# ELKS.net
KiCad netlist of a schematic drawn in EasyEDA Pro
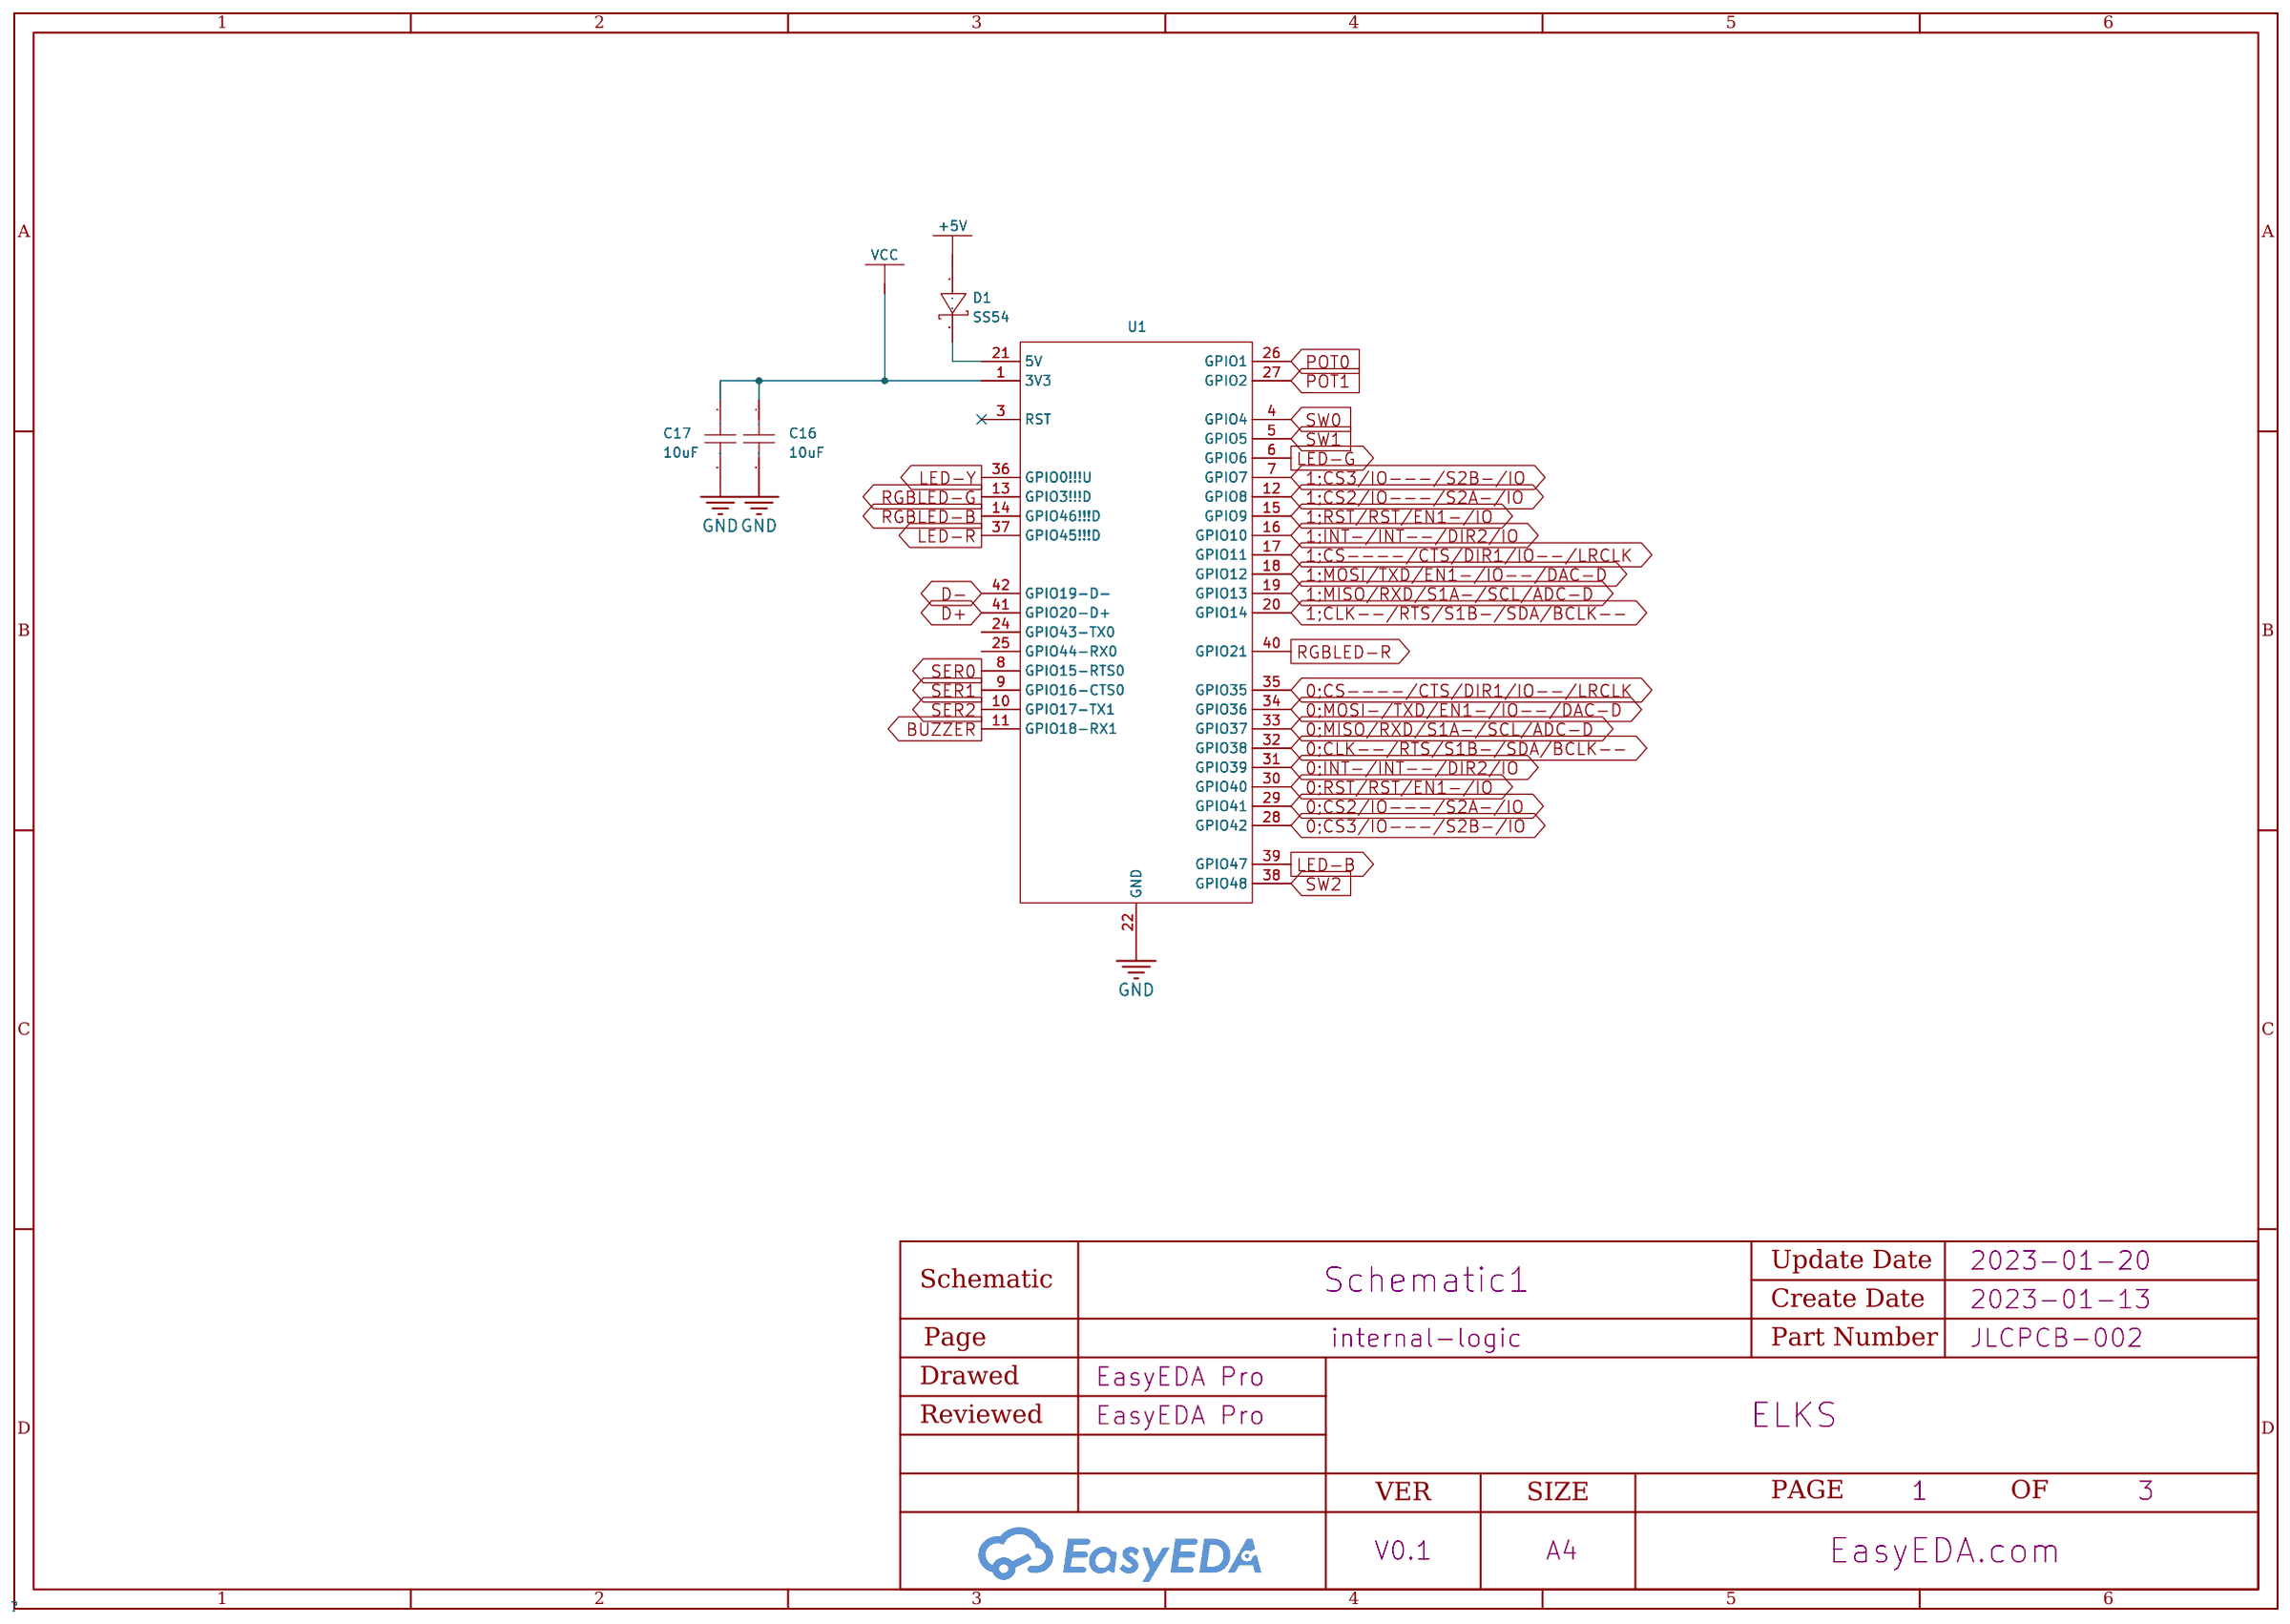
[diagram p0: internal-logic]
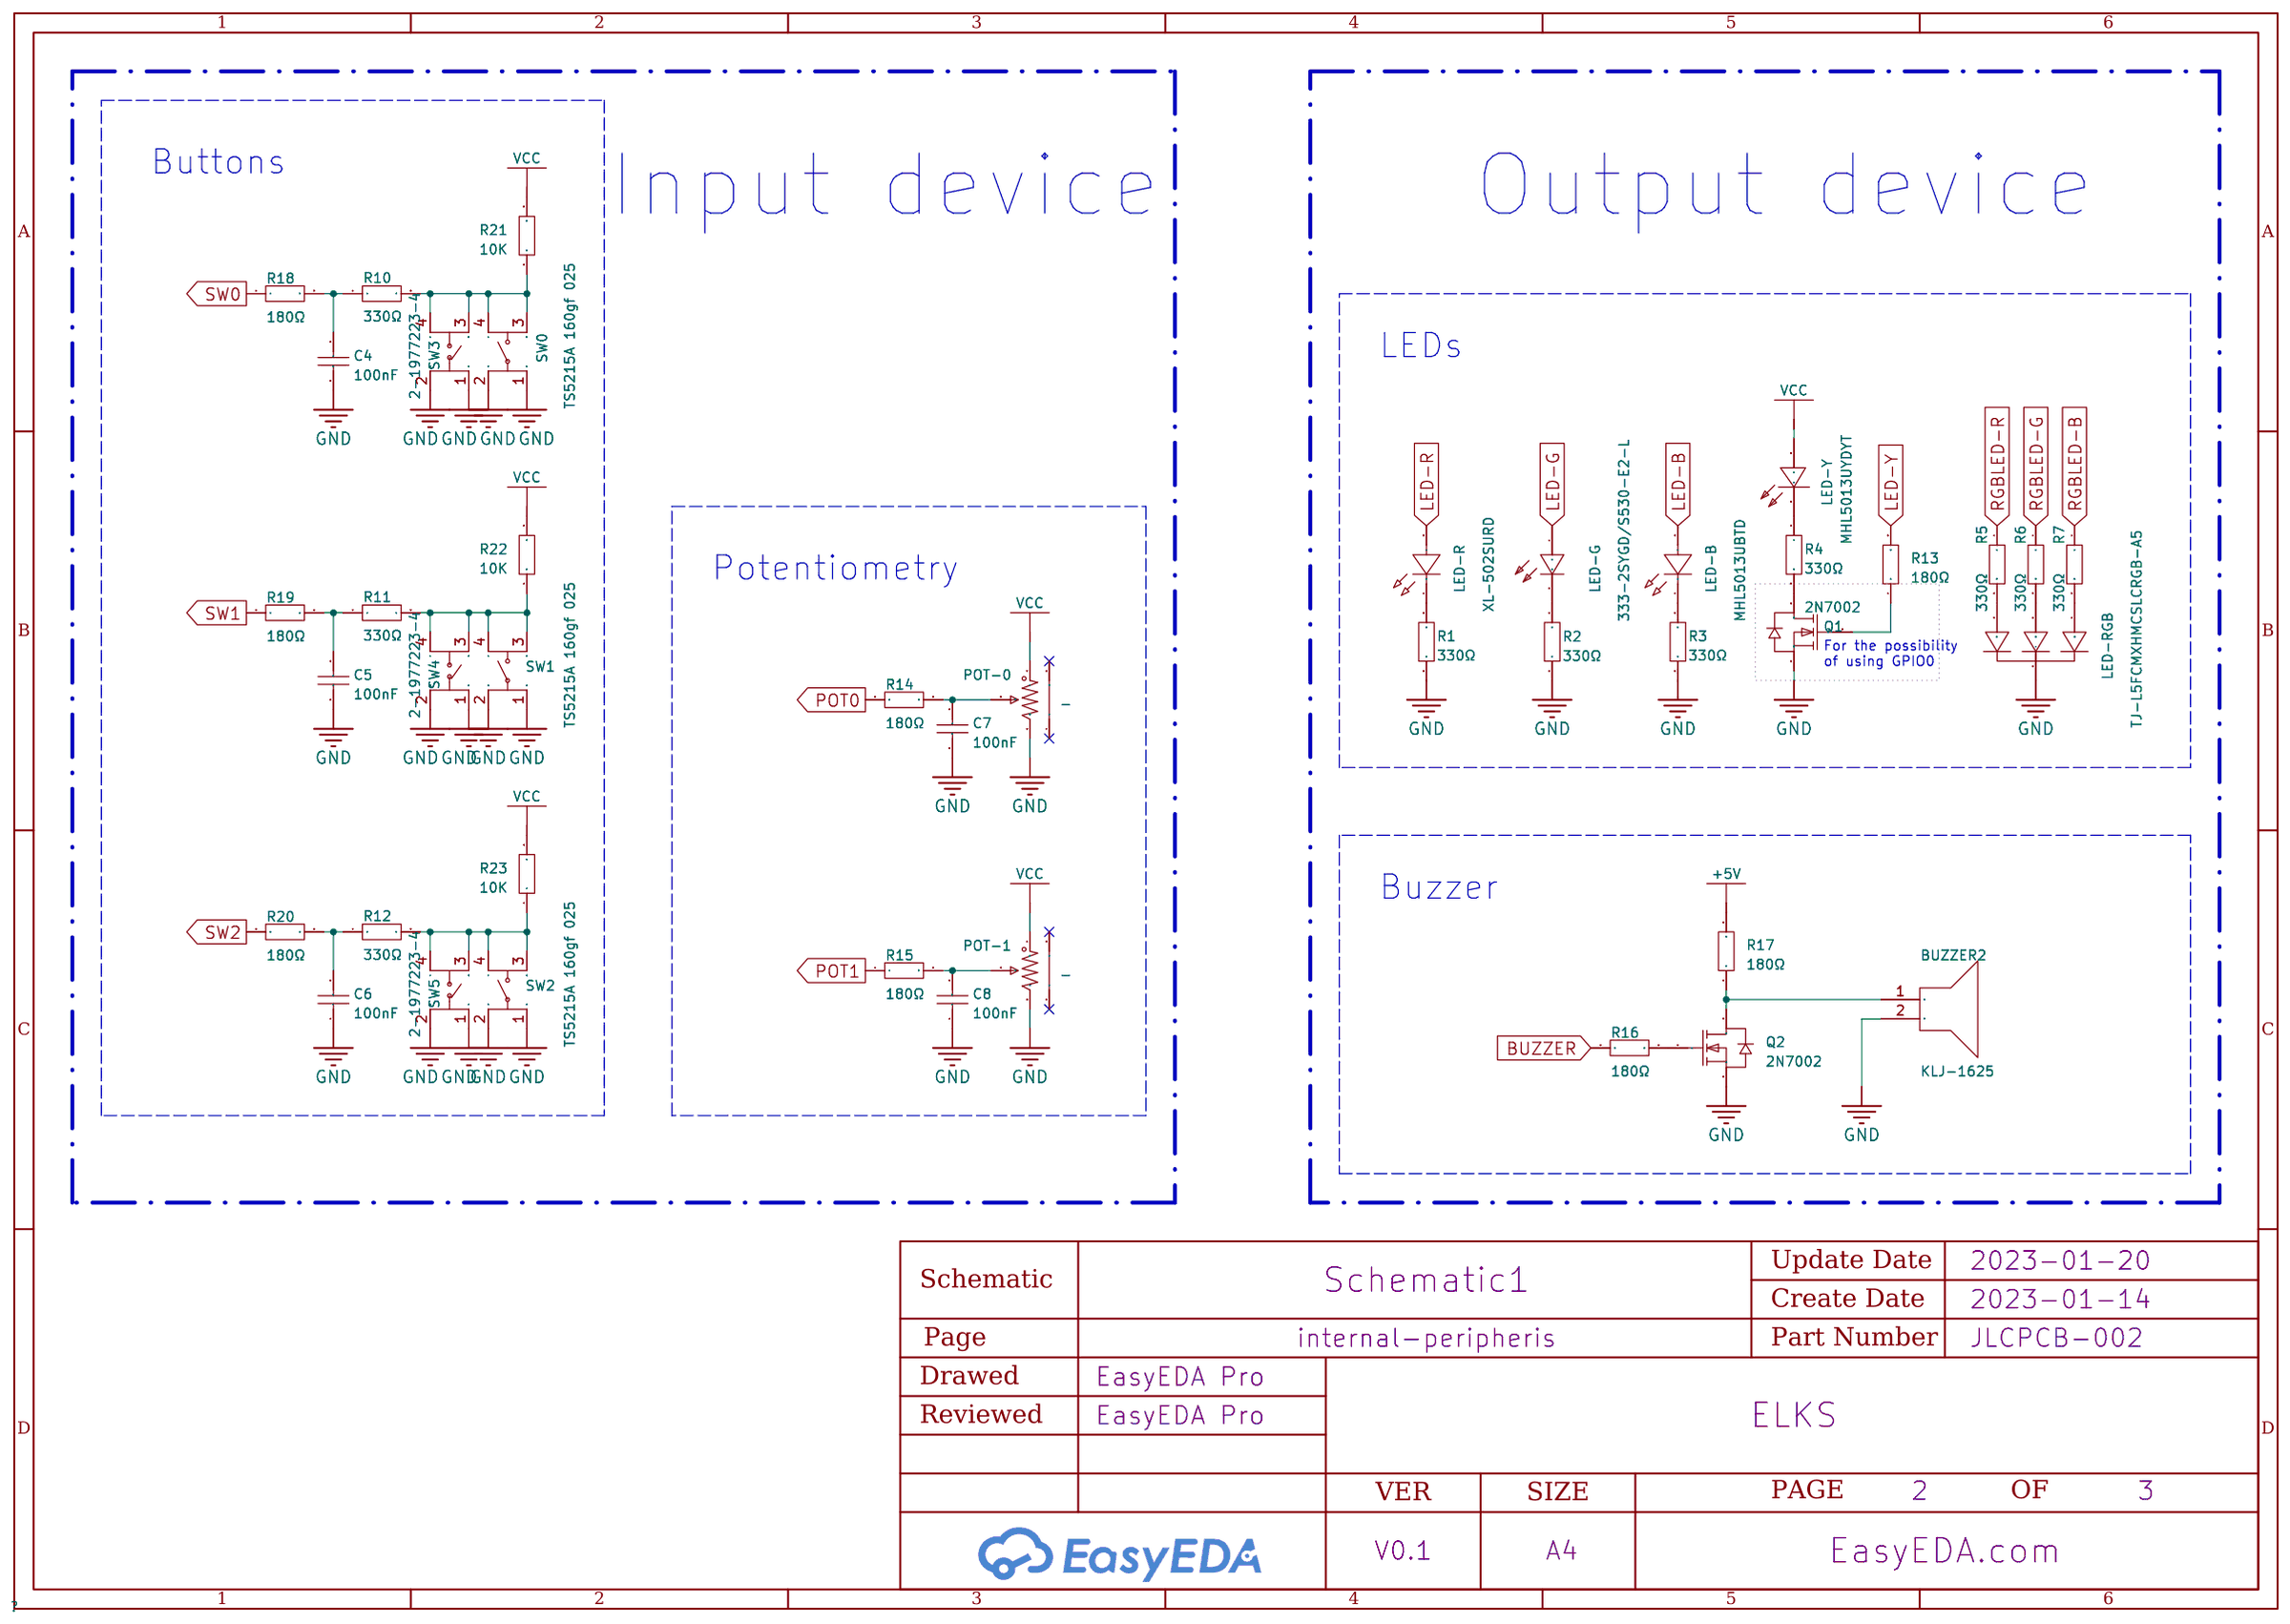
[diagram p1: internal-peripheris]
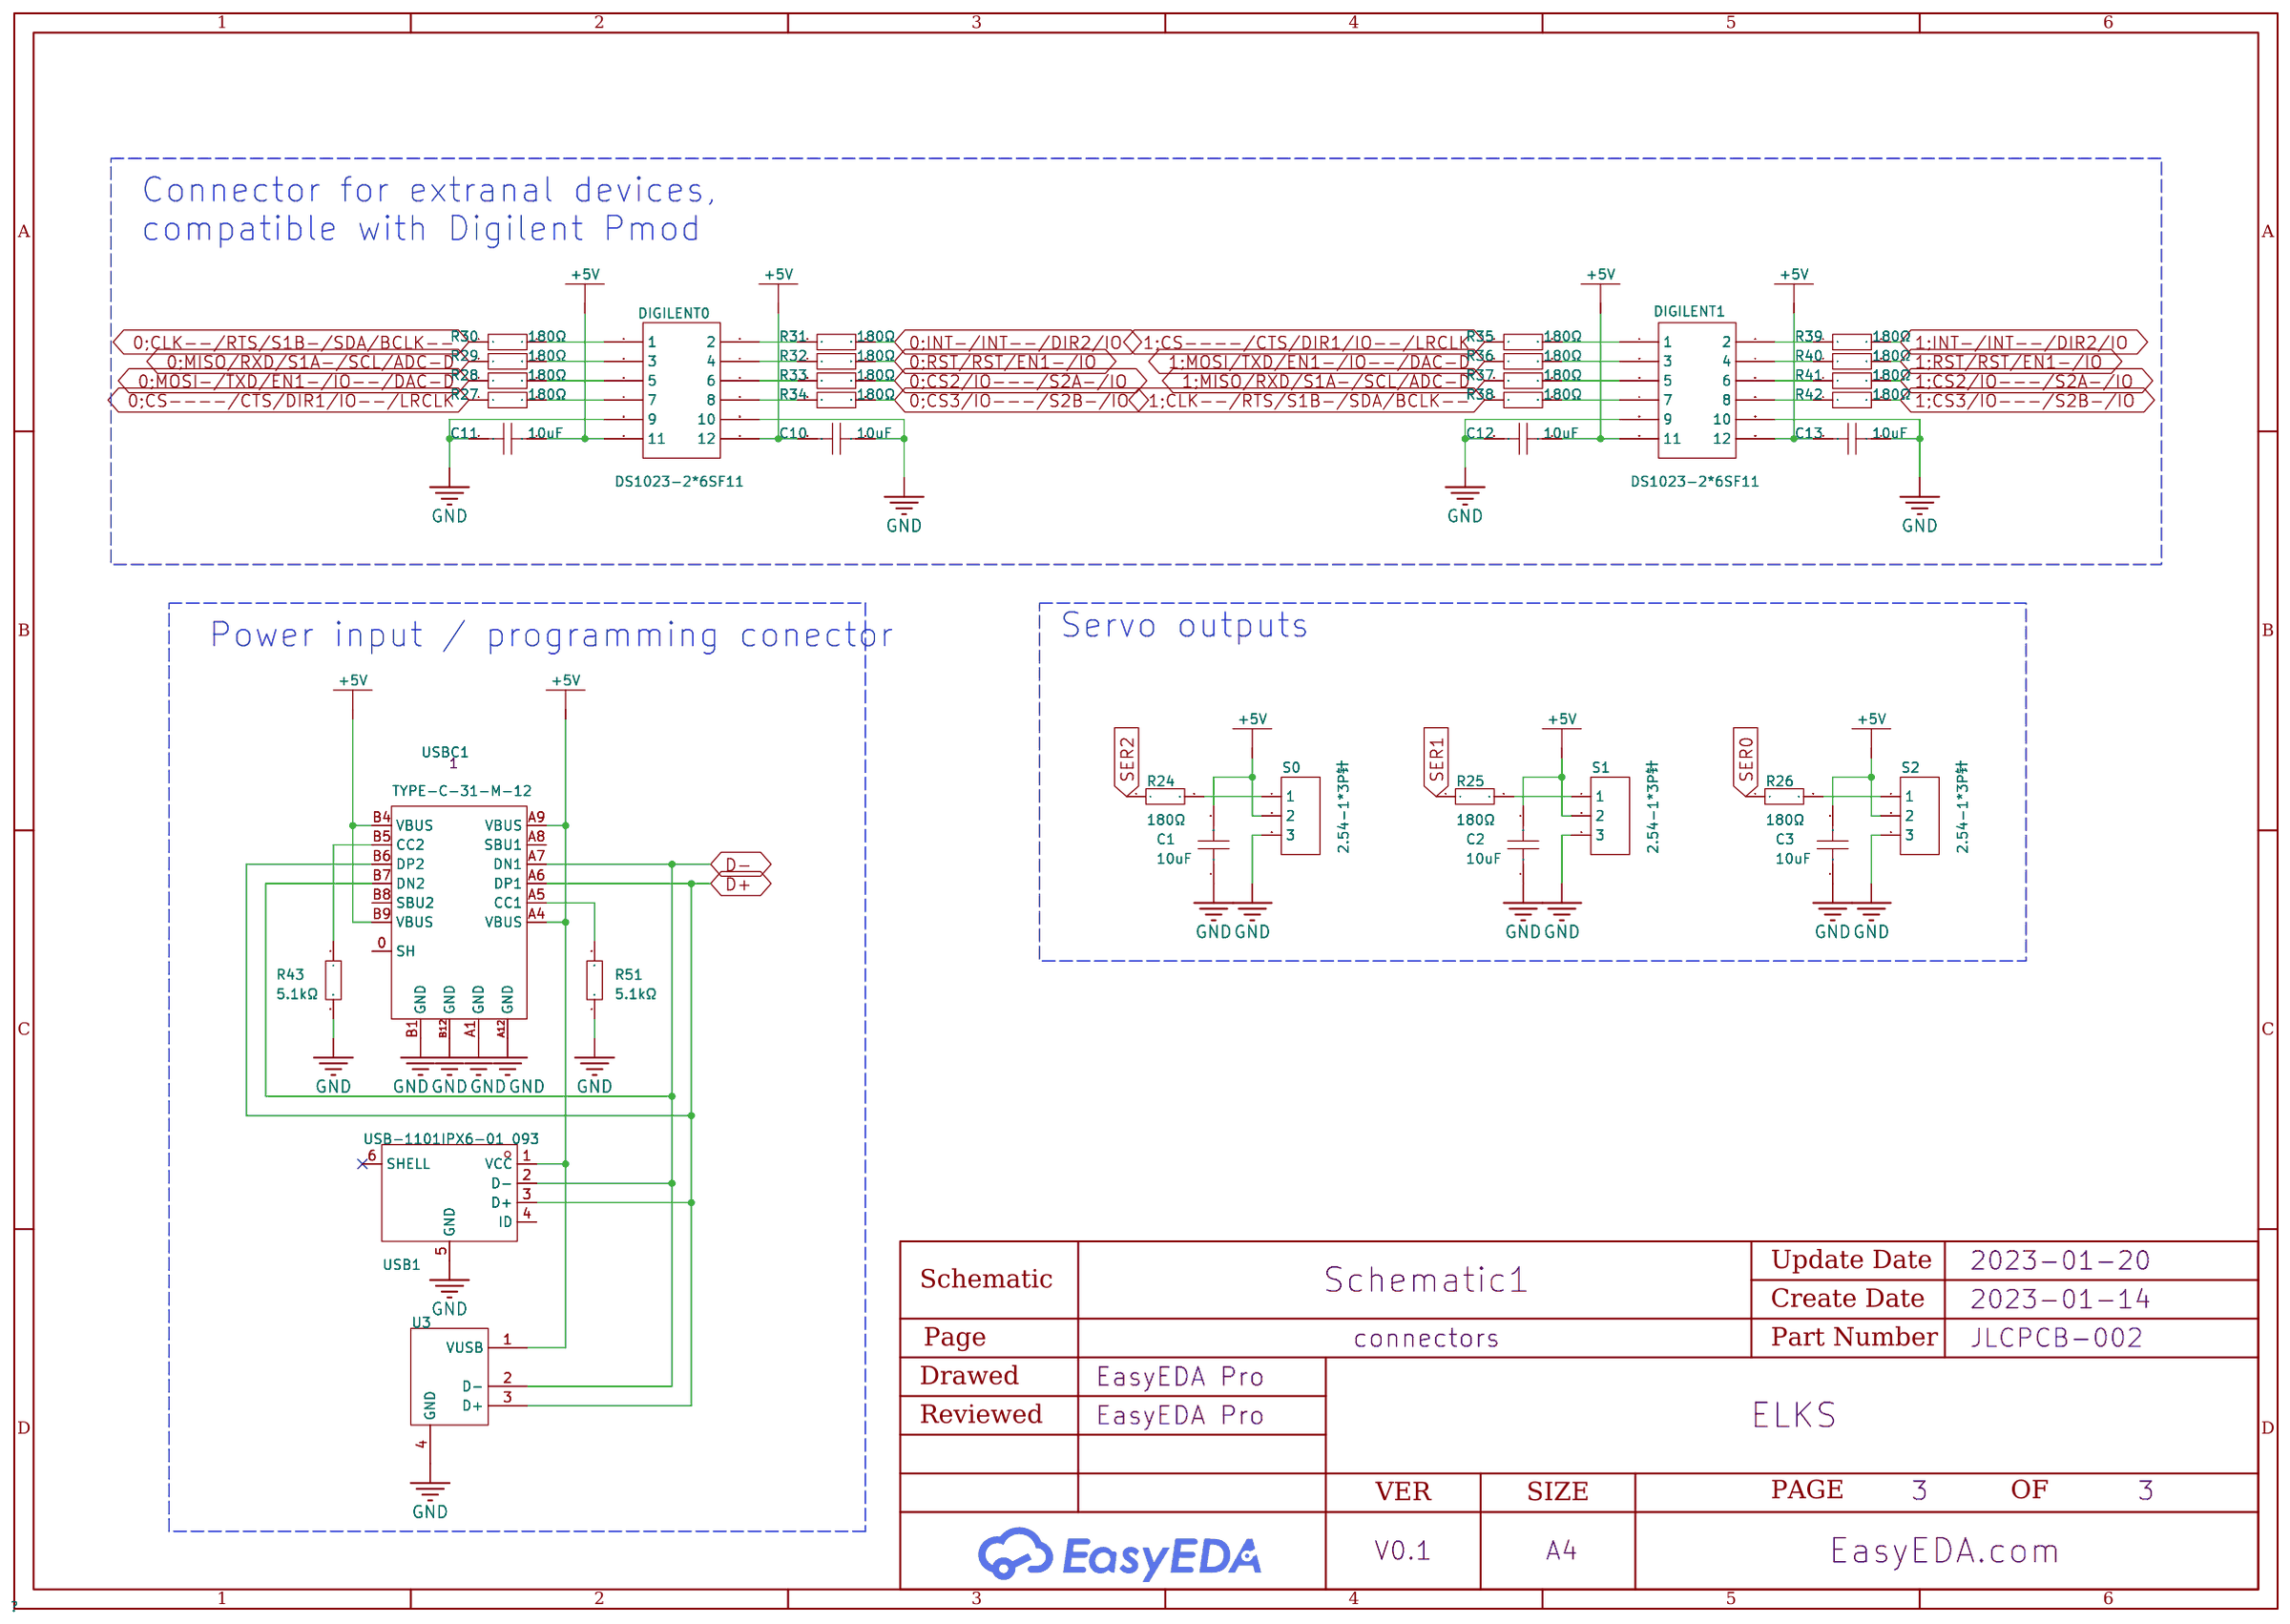
[diagram p2: connectors]

(export (version "E")
  (design (tool "Eeschema 10.0.6"))
  (components
    (comp (ref "C16")
      (value "10uF")
      (footprint "easyedapro:C0603")
      (fields
        (field (name "Manufacturer Part") "CL10A106MA8NRNC")
        (field (name "Manufacturer") "SAMSUNG(三星)")
        (field (name "Tolerance") "±20%")
      )
      (libsource (lib "easyedapro") (part "CL10A106MA8NRNC"))
    )
    (comp (ref "C17")
      (value "10uF")
      (footprint "easyedapro:C0603")
      (fields
        (field (name "Manufacturer Part") "CL10A106MA8NRNC")
        (field (name "Manufacturer") "SAMSUNG(三星)")
        (field (name "Tolerance") "±20%")
      )
      (libsource (lib "easyedapro") (part "CL10A106MA8NRNC"))
    )
    (comp (ref "D1")
      (value "SS54")
      (footprint "easyedapro:SMA_L4.4-W2.8-LS5.4-R-RD")
      (description "Reverse Voltage (Vr):40V Average Rectified Current (Io):5A Forward Voltage (Vf@If):550mV@5A")
      (fields (field (name "Manufacturer") "MDD"))
      (libsource (lib "easyedapro") (part "SS54_C22452"))
    )
    (comp (ref "U1") (value "~") (libsource (lib "easyedapro") (part "ESP32-S3-DevKitC-1")))
    (comp (ref "BUZZER2")
      (value "KLJ-1625")
      (footprint "easyedapro:BUZ-SMD_L16.0-W16.0")
      (fields (field (name "Manufacturer") "KELIKING(凯丽金)"))
      (libsource (lib "easyedapro") (part "KLJ-1625"))
    )
    (comp (ref "C4")
      (value "100nF")
      (footprint "easyedapro:C0402_NEW")
      (fields
        (field (name "Manufacturer Part") "CL05B104KO5NNNC")
        (field (name "Manufacturer") "SAMSUNG(三星)")
        (field (name "Tolerance") "±10%")
      )
      (libsource (lib "easyedapro") (part "CL05B104KO5NNNC"))
    )
    (comp (ref "C5")
      (value "100nF")
      (footprint "easyedapro:C0402_NEW")
      (fields
        (field (name "Manufacturer Part") "CL05B104KO5NNNC")
        (field (name "Manufacturer") "SAMSUNG(三星)")
        (field (name "Tolerance") "±10%")
      )
      (libsource (lib "easyedapro") (part "CL05B104KO5NNNC"))
    )
    (comp (ref "C6")
      (value "100nF")
      (footprint "easyedapro:C0402_NEW")
      (fields
        (field (name "Manufacturer Part") "CL05B104KO5NNNC")
        (field (name "Manufacturer") "SAMSUNG(三星)")
        (field (name "Tolerance") "±10%")
      )
      (libsource (lib "easyedapro") (part "CL05B104KO5NNNC"))
    )
    (comp (ref "C7")
      (value "100nF")
      (footprint "easyedapro:C0402_NEW")
      (fields
        (field (name "Manufacturer Part") "CL05B104KO5NNNC")
        (field (name "Manufacturer") "SAMSUNG(三星)")
        (field (name "Tolerance") "±10%")
      )
      (libsource (lib "easyedapro") (part "CL05B104KO5NNNC"))
    )
    (comp (ref "C8")
      (value "100nF")
      (footprint "easyedapro:C0402_NEW")
      (fields
        (field (name "Manufacturer Part") "CL05B104KO5NNNC")
        (field (name "Manufacturer") "SAMSUNG(三星)")
        (field (name "Tolerance") "±10%")
      )
      (libsource (lib "easyedapro") (part "CL05B104KO5NNNC"))
    )
    (comp (ref "LED-B")
      (value "MHL5013UBTD")
      (footprint "easyedapro:LED-TH_BD5.0-P2.54-L-RD_BLUE")
      (fields (field (name "Manufacturer") "MEIHUA(美华)"))
      (libsource (lib "easyedapro") (part "MHL5013UBTD"))
    )
    (comp (ref "LED-G")
      (value "333-2SYGD/S530-E2-L")
      (footprint "easyedapro:LED-TH_BD5.0-P2.54-FD")
      (fields (field (name "Manufacturer") "EVERLIGHT(亿光)"))
      (libsource (lib "easyedapro") (part "333-2SYGD/S530-E2-L"))
    )
    (comp (ref "LED-R")
      (value "XL-502SURD")
      (footprint "easyedapro:LED-TH_BD5.9-P2.54-RD_RED")
      (fields (field (name "Manufacturer") "XINGLIGHT(成兴光)"))
      (libsource (lib "easyedapro") (part "XL-502SURD"))
    )
    (comp (ref "LED-RGB")
      (value "TJ-L5FCMXHMCSLCRGB-A5")
      (footprint "easyedapro:LED-TH_4P-BD5.8-P1.30")
      (fields (field (name "Manufacturer") "TOGIALED(统佳)"))
      (libsource (lib "easyedapro") (part "TJ-L5FCMXHMCSLCRGB-A5"))
    )
    (comp (ref "LED-Y")
      (value "MHL5013UYDYT")
      (footprint "easyedapro:LED-TH_BD5.0-P2.54-L-RD_YELLOW")
      (fields (field (name "Manufacturer") "MEIHUA(美华)"))
      (libsource (lib "easyedapro") (part "MHL5013UYDYT"))
    )
    (comp (ref "POT-0")
      (value "-")
      (footprint "easyedapro:RES-ADJ-TH_RK09D1130C4G")
      (fields
        (field (name "Manufacturer Part") "RK09D1130C4G")
        (field (name "Manufacturer") "ALPSALPINE(阿尔卑斯阿尔派)")
      )
      (libsource (lib "easyedapro") (part "RK09D1130C4G"))
    )
    (comp (ref "POT-1")
      (value "-")
      (footprint "easyedapro:RES-ADJ-TH_RK09D1130C4G")
      (fields
        (field (name "Manufacturer Part") "RK09D1130C4G")
        (field (name "Manufacturer") "ALPSALPINE(阿尔卑斯阿尔派)")
      )
      (libsource (lib "easyedapro") (part "RK09D1130C4G"))
    )
    (comp (ref "Q1")
      (value "2N7002")
      (footprint "easyedapro:SOT-23-3_L2.9-W1.3-P1.90-LS2.4-BR")
      (fields (field (name "Manufacturer") "CJ(江苏长电/长晶)"))
      (libsource (lib "easyedapro") (part "2N7002"))
    )
    (comp (ref "Q2")
      (value "2N7002")
      (footprint "easyedapro:SOT-23-3_L2.9-W1.3-P1.90-LS2.4-BR")
      (fields (field (name "Manufacturer") "CJ(江苏长电/长晶)"))
      (libsource (lib "easyedapro") (part "2N7002"))
    )
    (comp (ref "R1")
      (value "330Ω")
      (footprint "easyedapro:R0603")
      (fields
        (field (name "Manufacturer Part") "0402WGF3300TCE")
        (field (name "Manufacturer") "UNI-ROYAL(厚声)")
      )
      (libsource (lib "easyedapro") (part "Res"))
    )
    (comp (ref "R2")
      (value "330Ω")
      (footprint "easyedapro:R0603")
      (fields
        (field (name "Manufacturer Part") "0402WGF3300TCE")
        (field (name "Manufacturer") "UNI-ROYAL(厚声)")
      )
      (libsource (lib "easyedapro") (part "Res"))
    )
    (comp (ref "R3")
      (value "330Ω")
      (footprint "easyedapro:R0603")
      (fields
        (field (name "Manufacturer Part") "0402WGF3300TCE")
        (field (name "Manufacturer") "UNI-ROYAL(厚声)")
      )
      (libsource (lib "easyedapro") (part "Res"))
    )
    (comp (ref "R4")
      (value "330Ω")
      (footprint "easyedapro:R0603")
      (fields
        (field (name "Manufacturer Part") "0402WGF3300TCE")
        (field (name "Manufacturer") "UNI-ROYAL(厚声)")
      )
      (libsource (lib "easyedapro") (part "Res"))
    )
    (comp (ref "R5")
      (value "330Ω")
      (footprint "easyedapro:R0603")
      (fields
        (field (name "Manufacturer Part") "0402WGF3300TCE")
        (field (name "Manufacturer") "UNI-ROYAL(厚声)")
      )
      (libsource (lib "easyedapro") (part "Res"))
    )
    (comp (ref "R6")
      (value "330Ω")
      (footprint "easyedapro:R0603")
      (fields
        (field (name "Manufacturer Part") "0402WGF3300TCE")
        (field (name "Manufacturer") "UNI-ROYAL(厚声)")
      )
      (libsource (lib "easyedapro") (part "Res"))
    )
    (comp (ref "R7")
      (value "330Ω")
      (footprint "easyedapro:R0603")
      (fields
        (field (name "Manufacturer Part") "0402WGF3300TCE")
        (field (name "Manufacturer") "UNI-ROYAL(厚声)")
      )
      (libsource (lib "easyedapro") (part "Res"))
    )
    (comp (ref "R10")
      (value "330Ω")
      (footprint "easyedapro:R0603")
      (fields
        (field (name "Manufacturer Part") "0402WGF3300TCE")
        (field (name "Manufacturer") "UNI-ROYAL(厚声)")
      )
      (libsource (lib "easyedapro") (part "Res"))
    )
    (comp (ref "R11")
      (value "330Ω")
      (footprint "easyedapro:R0603")
      (fields
        (field (name "Manufacturer Part") "0402WGF3300TCE")
        (field (name "Manufacturer") "UNI-ROYAL(厚声)")
      )
      (libsource (lib "easyedapro") (part "Res"))
    )
    (comp (ref "R12")
      (value "330Ω")
      (footprint "easyedapro:R0603")
      (fields
        (field (name "Manufacturer Part") "0402WGF3300TCE")
        (field (name "Manufacturer") "UNI-ROYAL(厚声)")
      )
      (libsource (lib "easyedapro") (part "Res"))
    )
    (comp (ref "R13")
      (value "180Ω")
      (footprint "easyedapro:R0603")
      (fields
        (field (name "Manufacturer Part") "0603WAF1800T5E")
        (field (name "Manufacturer") "UNI-ROYAL(厚声)")
      )
      (libsource (lib "easyedapro") (part "0603WAF1800T5E"))
    )
    (comp (ref "R14")
      (value "180Ω")
      (footprint "easyedapro:R0603")
      (fields
        (field (name "Manufacturer Part") "0603WAF1800T5E")
        (field (name "Manufacturer") "UNI-ROYAL(厚声)")
      )
      (libsource (lib "easyedapro") (part "0603WAF1800T5E"))
    )
    (comp (ref "R15")
      (value "180Ω")
      (footprint "easyedapro:R0603")
      (fields
        (field (name "Manufacturer Part") "0603WAF1800T5E")
        (field (name "Manufacturer") "UNI-ROYAL(厚声)")
      )
      (libsource (lib "easyedapro") (part "0603WAF1800T5E"))
    )
    (comp (ref "R16")
      (value "180Ω")
      (footprint "easyedapro:R0603")
      (fields
        (field (name "Manufacturer Part") "0603WAF1800T5E")
        (field (name "Manufacturer") "UNI-ROYAL(厚声)")
      )
      (libsource (lib "easyedapro") (part "0603WAF1800T5E"))
    )
    (comp (ref "R17")
      (value "180Ω")
      (footprint "easyedapro:R0603")
      (fields
        (field (name "Manufacturer Part") "0603WAF1800T5E")
        (field (name "Manufacturer") "UNI-ROYAL(厚声)")
      )
      (libsource (lib "easyedapro") (part "0603WAF1800T5E"))
    )
    (comp (ref "R18")
      (value "180Ω")
      (footprint "easyedapro:R0603")
      (fields
        (field (name "Manufacturer Part") "0603WAF1800T5E")
        (field (name "Manufacturer") "UNI-ROYAL(厚声)")
      )
      (libsource (lib "easyedapro") (part "0603WAF1800T5E"))
    )
    (comp (ref "R19")
      (value "180Ω")
      (footprint "easyedapro:R0603")
      (fields
        (field (name "Manufacturer Part") "0603WAF1800T5E")
        (field (name "Manufacturer") "UNI-ROYAL(厚声)")
      )
      (libsource (lib "easyedapro") (part "0603WAF1800T5E"))
    )
    (comp (ref "R20")
      (value "180Ω")
      (footprint "easyedapro:R0603")
      (fields
        (field (name "Manufacturer Part") "0603WAF1800T5E")
        (field (name "Manufacturer") "UNI-ROYAL(厚声)")
      )
      (libsource (lib "easyedapro") (part "0603WAF1800T5E"))
    )
    (comp (ref "R21")
      (value "10K")
      (footprint "easyedapro:R0603")
      (libsource (lib "easyedapro") (part "Res"))
    )
    (comp (ref "R22")
      (value "10K")
      (footprint "easyedapro:R0603")
      (libsource (lib "easyedapro") (part "Res"))
    )
    (comp (ref "R23")
      (value "10K")
      (footprint "easyedapro:R0603")
      (libsource (lib "easyedapro") (part "Res"))
    )
    (comp (ref "SW0")
      (value "TS5215A 160gf 025")
      (footprint "easyedapro:SW-SMD_4P-L5.2-W5.2-P3.70-LS6.4")
      (description "Switch Length:5.2mm Switch Width:5.2mm Switch Height:1.5mm")
      (fields (field (name "Manufacturer") "SHOU HAN(首韩)"))
      (libsource (lib "easyedapro") (part "TS5215A 160GF 025"))
    )
    (comp (ref "SW1")
      (value "TS5215A 160gf 025")
      (footprint "easyedapro:SW-SMD_4P-L5.2-W5.2-P3.70-LS6.4")
      (description "Switch Length:5.2mm Switch Width:5.2mm Switch Height:1.5mm")
      (fields (field (name "Manufacturer") "SHOU HAN(首韩)"))
      (libsource (lib "easyedapro") (part "TS5215A 160GF 025"))
    )
    (comp (ref "SW2")
      (value "TS5215A 160gf 025")
      (footprint "easyedapro:SW-SMD_4P-L5.2-W5.2-P3.70-LS6.4")
      (description "Switch Length:5.2mm Switch Width:5.2mm Switch Height:1.5mm")
      (fields (field (name "Manufacturer") "SHOU HAN(首韩)"))
      (libsource (lib "easyedapro") (part "TS5215A 160GF 025"))
    )
    (comp (ref "SW3")
      (value "2-1977223-4")
      (footprint "easyedapro:SW-SMD_4P-L6.0-W6.0-P4.50-LS10.0-BL")
      (fields (field (name "Manufacturer") "TE Connectivity(美国泰科)"))
      (libsource (lib "easyedapro") (part "2-1977223-4"))
    )
    (comp (ref "SW4")
      (value "2-1977223-4")
      (footprint "easyedapro:SW-SMD_4P-L6.0-W6.0-P4.50-LS10.0-BL")
      (fields (field (name "Manufacturer") "TE Connectivity(美国泰科)"))
      (libsource (lib "easyedapro") (part "2-1977223-4"))
    )
    (comp (ref "SW5")
      (value "2-1977223-4")
      (footprint "easyedapro:SW-SMD_4P-L6.0-W6.0-P4.50-LS10.0-BL")
      (fields (field (name "Manufacturer") "TE Connectivity(美国泰科)"))
      (libsource (lib "easyedapro") (part "2-1977223-4"))
    )
    (comp (ref "C1")
      (value "10uF")
      (footprint "easyedapro:C0603")
      (fields
        (field (name "Manufacturer Part") "CL10A106MA8NRNC")
        (field (name "Manufacturer") "SAMSUNG(三星)")
        (field (name "Tolerance") "±20%")
      )
      (libsource (lib "easyedapro") (part "CL10A106MA8NRNC"))
    )
    (comp (ref "C2")
      (value "10uF")
      (footprint "easyedapro:C0603")
      (fields
        (field (name "Manufacturer Part") "CL10A106MA8NRNC")
        (field (name "Manufacturer") "SAMSUNG(三星)")
        (field (name "Tolerance") "±20%")
      )
      (libsource (lib "easyedapro") (part "CL10A106MA8NRNC"))
    )
    (comp (ref "C3")
      (value "10uF")
      (footprint "easyedapro:C0603")
      (fields
        (field (name "Manufacturer Part") "CL10A106MA8NRNC")
        (field (name "Manufacturer") "SAMSUNG(三星)")
        (field (name "Tolerance") "±20%")
      )
      (libsource (lib "easyedapro") (part "CL10A106MA8NRNC"))
    )
    (comp (ref "C10")
      (value "10uF")
      (footprint "easyedapro:C0603")
      (fields
        (field (name "Manufacturer Part") "CL10A106MA8NRNC")
        (field (name "Manufacturer") "SAMSUNG(三星)")
        (field (name "Tolerance") "±20%")
      )
      (libsource (lib "easyedapro") (part "CL10A106MA8NRNC"))
    )
    (comp (ref "C11")
      (value "10uF")
      (footprint "easyedapro:C0603")
      (fields
        (field (name "Manufacturer Part") "CL10A106MA8NRNC")
        (field (name "Manufacturer") "SAMSUNG(三星)")
        (field (name "Tolerance") "±20%")
      )
      (libsource (lib "easyedapro") (part "CL10A106MA8NRNC"))
    )
    (comp (ref "C12")
      (value "10uF")
      (footprint "easyedapro:C0603")
      (fields
        (field (name "Manufacturer Part") "CL10A106MA8NRNC")
        (field (name "Manufacturer") "SAMSUNG(三星)")
        (field (name "Tolerance") "±20%")
      )
      (libsource (lib "easyedapro") (part "CL10A106MA8NRNC"))
    )
    (comp (ref "C13")
      (value "10uF")
      (footprint "easyedapro:C0603")
      (fields
        (field (name "Manufacturer Part") "CL10A106MA8NRNC")
        (field (name "Manufacturer") "SAMSUNG(三星)")
        (field (name "Tolerance") "±20%")
      )
      (libsource (lib "easyedapro") (part "CL10A106MA8NRNC"))
    )
    (comp (ref "DIGILENT0")
      (value "DS1023-2*6SF11")
      (footprint "easyedapro:HDR-TH_12P-P2.54-V-F-R2-C6-S2.54")
      (fields (field (name "Manufacturer") "CONNFLY"))
      (libsource (lib "easyedapro") (part "DS1023-2*6SF11"))
    )
    (comp (ref "DIGILENT1")
      (value "DS1023-2*6SF11")
      (footprint "easyedapro:HDR-TH_12P-P2.54-V-F-R2-C6-S2.54")
      (fields (field (name "Manufacturer") "CONNFLY"))
      (libsource (lib "easyedapro") (part "DS1023-2*6SF11"))
    )
    (comp (ref "R24")
      (value "180Ω")
      (footprint "easyedapro:R0603")
      (fields
        (field (name "Manufacturer Part") "0603WAF1800T5E")
        (field (name "Manufacturer") "UNI-ROYAL(厚声)")
      )
      (libsource (lib "easyedapro") (part "0603WAF1800T5E"))
    )
    (comp (ref "R25")
      (value "180Ω")
      (footprint "easyedapro:R0603")
      (fields
        (field (name "Manufacturer Part") "0603WAF1800T5E")
        (field (name "Manufacturer") "UNI-ROYAL(厚声)")
      )
      (libsource (lib "easyedapro") (part "0603WAF1800T5E"))
    )
    (comp (ref "R26")
      (value "180Ω")
      (footprint "easyedapro:R0603")
      (fields
        (field (name "Manufacturer Part") "0603WAF1800T5E")
        (field (name "Manufacturer") "UNI-ROYAL(厚声)")
      )
      (libsource (lib "easyedapro") (part "0603WAF1800T5E"))
    )
    (comp (ref "R27")
      (value "180Ω")
      (footprint "easyedapro:R0603")
      (fields
        (field (name "Manufacturer Part") "0603WAF1800T5E")
        (field (name "Manufacturer") "UNI-ROYAL(厚声)")
      )
      (libsource (lib "easyedapro") (part "0603WAF1800T5E"))
    )
    (comp (ref "R28")
      (value "180Ω")
      (footprint "easyedapro:R0603")
      (fields
        (field (name "Manufacturer Part") "0603WAF1800T5E")
        (field (name "Manufacturer") "UNI-ROYAL(厚声)")
      )
      (libsource (lib "easyedapro") (part "0603WAF1800T5E"))
    )
    (comp (ref "R29")
      (value "180Ω")
      (footprint "easyedapro:R0603")
      (fields
        (field (name "Manufacturer Part") "0603WAF1800T5E")
        (field (name "Manufacturer") "UNI-ROYAL(厚声)")
      )
      (libsource (lib "easyedapro") (part "0603WAF1800T5E"))
    )
    (comp (ref "R30")
      (value "180Ω")
      (footprint "easyedapro:R0603")
      (fields
        (field (name "Manufacturer Part") "0603WAF1800T5E")
        (field (name "Manufacturer") "UNI-ROYAL(厚声)")
      )
      (libsource (lib "easyedapro") (part "0603WAF1800T5E"))
    )
    (comp (ref "R31")
      (value "180Ω")
      (footprint "easyedapro:R0603")
      (fields
        (field (name "Manufacturer Part") "0603WAF1800T5E")
        (field (name "Manufacturer") "UNI-ROYAL(厚声)")
      )
      (libsource (lib "easyedapro") (part "0603WAF1800T5E"))
    )
    (comp (ref "R32")
      (value "180Ω")
      (footprint "easyedapro:R0603")
      (fields
        (field (name "Manufacturer Part") "0603WAF1800T5E")
        (field (name "Manufacturer") "UNI-ROYAL(厚声)")
      )
      (libsource (lib "easyedapro") (part "0603WAF1800T5E"))
    )
    (comp (ref "R33")
      (value "180Ω")
      (footprint "easyedapro:R0603")
      (fields
        (field (name "Manufacturer Part") "0603WAF1800T5E")
        (field (name "Manufacturer") "UNI-ROYAL(厚声)")
      )
      (libsource (lib "easyedapro") (part "0603WAF1800T5E"))
    )
    (comp (ref "R34")
      (value "180Ω")
      (footprint "easyedapro:R0603")
      (fields
        (field (name "Manufacturer Part") "0603WAF1800T5E")
        (field (name "Manufacturer") "UNI-ROYAL(厚声)")
      )
      (libsource (lib "easyedapro") (part "0603WAF1800T5E"))
    )
    (comp (ref "R35")
      (value "180Ω")
      (footprint "easyedapro:R0603")
      (fields
        (field (name "Manufacturer Part") "0603WAF1800T5E")
        (field (name "Manufacturer") "UNI-ROYAL(厚声)")
      )
      (libsource (lib "easyedapro") (part "0603WAF1800T5E"))
    )
    (comp (ref "R36")
      (value "180Ω")
      (footprint "easyedapro:R0603")
      (fields
        (field (name "Manufacturer Part") "0603WAF1800T5E")
        (field (name "Manufacturer") "UNI-ROYAL(厚声)")
      )
      (libsource (lib "easyedapro") (part "0603WAF1800T5E"))
    )
    (comp (ref "R37")
      (value "180Ω")
      (footprint "easyedapro:R0603")
      (fields
        (field (name "Manufacturer Part") "0603WAF1800T5E")
        (field (name "Manufacturer") "UNI-ROYAL(厚声)")
      )
      (libsource (lib "easyedapro") (part "0603WAF1800T5E"))
    )
    (comp (ref "R38")
      (value "180Ω")
      (footprint "easyedapro:R0603")
      (fields
        (field (name "Manufacturer Part") "0603WAF1800T5E")
        (field (name "Manufacturer") "UNI-ROYAL(厚声)")
      )
      (libsource (lib "easyedapro") (part "0603WAF1800T5E"))
    )
    (comp (ref "R39")
      (value "180Ω")
      (footprint "easyedapro:R0603")
      (fields
        (field (name "Manufacturer Part") "0603WAF1800T5E")
        (field (name "Manufacturer") "UNI-ROYAL(厚声)")
      )
      (libsource (lib "easyedapro") (part "0603WAF1800T5E"))
    )
    (comp (ref "R40")
      (value "180Ω")
      (footprint "easyedapro:R0603")
      (fields
        (field (name "Manufacturer Part") "0603WAF1800T5E")
        (field (name "Manufacturer") "UNI-ROYAL(厚声)")
      )
      (libsource (lib "easyedapro") (part "0603WAF1800T5E"))
    )
    (comp (ref "R41")
      (value "180Ω")
      (footprint "easyedapro:R0603")
      (fields
        (field (name "Manufacturer Part") "0603WAF1800T5E")
        (field (name "Manufacturer") "UNI-ROYAL(厚声)")
      )
      (libsource (lib "easyedapro") (part "0603WAF1800T5E"))
    )
    (comp (ref "R42")
      (value "180Ω")
      (footprint "easyedapro:R0603")
      (fields
        (field (name "Manufacturer Part") "0603WAF1800T5E")
        (field (name "Manufacturer") "UNI-ROYAL(厚声)")
      )
      (libsource (lib "easyedapro") (part "0603WAF1800T5E"))
    )
    (comp (ref "R43")
      (value "5.1kΩ")
      (footprint "easyedapro:R0603")
      (fields
        (field (name "Manufacturer Part") "RC0603FR-075K1L")
        (field (name "Manufacturer") "YAGEO(国巨)")
        (field (name "Tolerance") "±1%")
      )
      (libsource (lib "easyedapro") (part "RC0603FR-075K1L"))
    )
    (comp (ref "R51")
      (value "5.1kΩ")
      (footprint "easyedapro:R0603")
      (fields
        (field (name "Manufacturer Part") "RC0603FR-075K1L")
        (field (name "Manufacturer") "YAGEO(国巨)")
        (field (name "Tolerance") "±1%")
      )
      (libsource (lib "easyedapro") (part "RC0603FR-075K1L"))
    )
    (comp (ref "S0")
      (value "2.54-1*3P针")
      (footprint "easyedapro:HDR-TH_3P-P2.54-V-M-1")
      (fields (field (name "Manufacturer") "BOOMELE(博穆精密)"))
      (libsource (lib "easyedapro") (part "Header-Male-2.54_1x3"))
    )
    (comp (ref "S1")
      (value "2.54-1*3P针")
      (footprint "easyedapro:HDR-TH_3P-P2.54-V-M-1")
      (fields (field (name "Manufacturer") "BOOMELE(博穆精密)"))
      (libsource (lib "easyedapro") (part "Header-Male-2.54_1x3"))
    )
    (comp (ref "S2")
      (value "2.54-1*3P针")
      (footprint "easyedapro:HDR-TH_3P-P2.54-V-M-1")
      (fields (field (name "Manufacturer") "BOOMELE(博穆精密)"))
      (libsource (lib "easyedapro") (part "Header-Male-2.54_1x3"))
    )
    (comp (ref "U3")
      (value "~")
      (footprint "easyedapro:usb-PCB")
      (libsource (lib "easyedapro") (part "USB_B_Micro"))
    )
    (comp (ref "USB1")
      (value "USB-1101IPX6-01 093")
      (footprint "easyedapro:MICRO-USB-SMD_USB-1101IPX6-01-093")
      (fields (field (name "Manufacturer") "SHOU HAN(首韩)"))
      (libsource (lib "easyedapro") (part "USB-1101IPX6-01 093"))
    )
    (comp (ref "USBC1")
      (value "TYPE-C-31-M-12")
      (footprint "easyedapro:USB-C_SMD-TYPE-C-31-M-12")
      (fields (field (name "Manufacturer") "韩国韩荣") (field (name "NUMBER") "1"))
      (libsource (lib "easyedapro") (part "TYPE-C-31-M-12"))
    )
  )
  (nets
    (net (code "1") (name "+5V") (class "Default")
      (node (ref "C1") (pin "2") (pinfunction "2_2") (pintype "input"))
      (node (ref "C10") (pin "2") (pinfunction "2_2") (pintype "input"))
      (node (ref "C11") (pin "1") (pinfunction "1_1") (pintype "input"))
      (node (ref "C12") (pin "1") (pinfunction "1_1") (pintype "input"))
      (node (ref "C13") (pin "2") (pinfunction "2_2") (pintype "input"))
      (node (ref "C2") (pin "2") (pinfunction "2_2") (pintype "input"))
      (node (ref "C3") (pin "2") (pinfunction "2_2") (pintype "input"))
      (node (ref "D1") (pin "1") (pinfunction "A_1") (pintype "input"))
      (node (ref "DIGILENT0") (pin "11") (pinfunction "11_11") (pintype "input"))
      (node (ref "DIGILENT0") (pin "12") (pinfunction "12_12") (pintype "input"))
      (node (ref "DIGILENT1") (pin "11") (pinfunction "11_11") (pintype "input"))
      (node (ref "DIGILENT1") (pin "12") (pinfunction "12_12") (pintype "input"))
      (node (ref "R17") (pin "2") (pinfunction "2_2") (pintype "input"))
      (node (ref "S0") (pin "2") (pinfunction "2_2") (pintype "input"))
      (node (ref "S1") (pin "2") (pinfunction "2_2") (pintype "input"))
      (node (ref "S2") (pin "2") (pinfunction "2_2") (pintype "input"))
      (node (ref "U3") (pin "1") (pinfunction "VUSB_1") (pintype "input"))
      (node (ref "USB1") (pin "1") (pinfunction "VCC_1") (pintype "input"))
      (node (ref "USBC1") (pin "A4") (pinfunction "VBUS_A4") (pintype "input"))
      (node (ref "USBC1") (pin "A9") (pinfunction "VBUS_A9") (pintype "input"))
      (node (ref "USBC1") (pin "B4") (pinfunction "VBUS_B4") (pintype "input"))
      (node (ref "USBC1") (pin "B9") (pinfunction "VBUS_B9") (pintype "input"))
    )
    (net (code "2") (name "0;CLK--{slash}RTS{slash}S1B-{slash}SDA{slash}BCLK--") (class "Default")
      (node (ref "R30") (pin "1") (pinfunction "1_1") (pintype "input"))
      (node (ref "U1") (pin "32") (pinfunction "GPIO38_32") (pintype "input"))
    )
    (net (code "3") (name "0;CS----{slash}CTS{slash}DIR1{slash}IO--{slash}LRCLK") (class "Default")
      (node (ref "R27") (pin "1") (pinfunction "1_1") (pintype "input"))
      (node (ref "U1") (pin "35") (pinfunction "GPIO35_35") (pintype "input"))
    )
    (net (code "4") (name "0;CS2{slash}IO---{slash}S2A-{slash}IO") (class "Default")
      (node (ref "R33") (pin "2") (pinfunction "2_2") (pintype "input"))
      (node (ref "U1") (pin "29") (pinfunction "GPIO41_29") (pintype "input"))
    )
    (net (code "5") (name "0;CS3{slash}IO---{slash}S2B-{slash}IO") (class "Default")
      (node (ref "R34") (pin "2") (pinfunction "2_2") (pintype "input"))
      (node (ref "U1") (pin "28") (pinfunction "GPIO42_28") (pintype "input"))
    )
    (net (code "6") (name "0;INT-{slash}INT--{slash}DIR2{slash}IO") (class "Default")
      (node (ref "R31") (pin "2") (pinfunction "2_2") (pintype "input"))
      (node (ref "U1") (pin "31") (pinfunction "GPIO39_31") (pintype "input"))
    )
    (net (code "7") (name "0;MISO{slash}RXD{slash}S1A-{slash}SCL{slash}ADC-D") (class "Default")
      (node (ref "R29") (pin "1") (pinfunction "1_1") (pintype "input"))
      (node (ref "U1") (pin "33") (pinfunction "GPIO37_33") (pintype "input"))
    )
    (net (code "8") (name "0;MOSI-{slash}TXD{slash}EN1-{slash}IO--{slash}DAC-D") (class "Default")
      (node (ref "R28") (pin "1") (pinfunction "1_1") (pintype "input"))
      (node (ref "U1") (pin "34") (pinfunction "GPIO36_34") (pintype "input"))
    )
    (net (code "9") (name "0;RST{slash}RST{slash}EN1-{slash}IO") (class "Default")
      (node (ref "R32") (pin "2") (pinfunction "2_2") (pintype "input"))
      (node (ref "U1") (pin "30") (pinfunction "GPIO40_30") (pintype "input"))
    )
    (net (code "10") (name "1;CLK--{slash}RTS{slash}S1B-{slash}SDA{slash}BCLK--") (class "Default")
      (node (ref "R38") (pin "1") (pinfunction "1_1") (pintype "input"))
      (node (ref "U1") (pin "20") (pinfunction "GPIO14_20") (pintype "input"))
    )
    (net (code "11") (name "1;CS----{slash}CTS{slash}DIR1{slash}IO--{slash}LRCLK") (class "Default")
      (node (ref "R35") (pin "1") (pinfunction "1_1") (pintype "input"))
      (node (ref "U1") (pin "17") (pinfunction "GPIO11_17") (pintype "input"))
    )
    (net (code "12") (name "1;CS2{slash}IO---{slash}S2A-{slash}IO") (class "Default")
      (node (ref "R41") (pin "2") (pinfunction "2_2") (pintype "input"))
      (node (ref "U1") (pin "12") (pinfunction "GPIO8_12") (pintype "input"))
    )
    (net (code "13") (name "1;CS3{slash}IO---{slash}S2B-{slash}IO") (class "Default")
      (node (ref "R42") (pin "2") (pinfunction "2_2") (pintype "input"))
      (node (ref "U1") (pin "7") (pinfunction "GPIO7_7") (pintype "input"))
    )
    (net (code "14") (name "1;INT-{slash}INT--{slash}DIR2{slash}IO") (class "Default")
      (node (ref "R39") (pin "2") (pinfunction "2_2") (pintype "input"))
      (node (ref "U1") (pin "16") (pinfunction "GPIO10_16") (pintype "input"))
    )
    (net (code "15") (name "1;MISO{slash}RXD{slash}S1A-{slash}SCL{slash}ADC-D") (class "Default")
      (node (ref "R37") (pin "1") (pinfunction "1_1") (pintype "input"))
      (node (ref "U1") (pin "19") (pinfunction "GPIO13_19") (pintype "input"))
    )
    (net (code "16") (name "1;MOSI{slash}TXD{slash}EN1-{slash}IO--{slash}DAC-D") (class "Default")
      (node (ref "R36") (pin "1") (pinfunction "1_1") (pintype "input"))
      (node (ref "U1") (pin "18") (pinfunction "GPIO12_18") (pintype "input"))
    )
    (net (code "17") (name "1;RST{slash}RST{slash}EN1-{slash}IO") (class "Default")
      (node (ref "R40") (pin "2") (pinfunction "2_2") (pintype "input"))
      (node (ref "U1") (pin "15") (pinfunction "GPIO9_15") (pintype "input"))
    )
    (net (code "18") (name "BUZZER") (class "Default")
      (node (ref "R16") (pin "1") (pinfunction "1_1") (pintype "input"))
      (node (ref "U1") (pin "11") (pinfunction "GPIO18-RX1_11") (pintype "input"))
    )
    (net (code "19") (name "D+") (class "Default")
      (node (ref "U1") (pin "41") (pinfunction "GPIO20-D+_41") (pintype "input"))
      (node (ref "U3") (pin "3") (pinfunction "D+_3") (pintype "input"))
      (node (ref "USB1") (pin "3") (pinfunction "D+_3") (pintype "input"))
      (node (ref "USBC1") (pin "A6") (pinfunction "DP1_A6") (pintype "input"))
      (node (ref "USBC1") (pin "B6") (pinfunction "DP2_B6") (pintype "input"))
    )
    (net (code "20") (name "D-") (class "Default")
      (node (ref "U1") (pin "42") (pinfunction "GPIO19-D-_42") (pintype "input"))
      (node (ref "U3") (pin "2") (pinfunction "D-_2") (pintype "input"))
      (node (ref "USB1") (pin "2") (pinfunction "D-_2") (pintype "input"))
      (node (ref "USBC1") (pin "A7") (pinfunction "DN1_A7") (pintype "input"))
      (node (ref "USBC1") (pin "B7") (pinfunction "DN2_B7") (pintype "input"))
    )
    (net (code "21") (name "GND") (class "Default")
      (node (ref "BUZZER2") (pin "2") (pinfunction "2_2") (pintype "input"))
      (node (ref "C1") (pin "1") (pinfunction "1_1") (pintype "input"))
      (node (ref "C10") (pin "1") (pinfunction "1_1") (pintype "input"))
      (node (ref "C11") (pin "2") (pinfunction "2_2") (pintype "input"))
      (node (ref "C12") (pin "2") (pinfunction "2_2") (pintype "input"))
      (node (ref "C13") (pin "1") (pinfunction "1_1") (pintype "input"))
      (node (ref "C16") (pin "2") (pinfunction "2_2") (pintype "input"))
      (node (ref "C17") (pin "2") (pinfunction "2_2") (pintype "input"))
      (node (ref "C2") (pin "1") (pinfunction "1_1") (pintype "input"))
      (node (ref "C3") (pin "1") (pinfunction "1_1") (pintype "input"))
      (node (ref "C4") (pin "1") (pinfunction "1_1") (pintype "input"))
      (node (ref "C5") (pin "1") (pinfunction "1_1") (pintype "input"))
      (node (ref "C6") (pin "1") (pinfunction "1_1") (pintype "input"))
      (node (ref "C7") (pin "1") (pinfunction "1_1") (pintype "input"))
      (node (ref "C8") (pin "1") (pinfunction "1_1") (pintype "input"))
      (node (ref "DIGILENT0") (pin "10") (pinfunction "10_10") (pintype "input"))
      (node (ref "DIGILENT0") (pin "9") (pinfunction "9_9") (pintype "input"))
      (node (ref "DIGILENT1") (pin "10") (pinfunction "10_10") (pintype "input"))
      (node (ref "DIGILENT1") (pin "9") (pinfunction "9_9") (pintype "input"))
      (node (ref "LED-RGB") (pin "2") (pinfunction "-_2") (pintype "input"))
      (node (ref "POT-0") (pin "3") (pinfunction "3_3") (pintype "input"))
      (node (ref "POT-1") (pin "3") (pinfunction "3_3") (pintype "input"))
      (node (ref "Q1") (pin "2") (pinfunction "S_2") (pintype "input"))
      (node (ref "Q2") (pin "2") (pinfunction "S_2") (pintype "input"))
      (node (ref "R1") (pin "2") (pinfunction "2_2") (pintype "input"))
      (node (ref "R2") (pin "2") (pinfunction "2_2") (pintype "input"))
      (node (ref "R3") (pin "2") (pinfunction "2_2") (pintype "input"))
      (node (ref "R43") (pin "2") (pinfunction "2_2") (pintype "input"))
      (node (ref "R51") (pin "1") (pinfunction "1_1") (pintype "input"))
      (node (ref "S0") (pin "3") (pinfunction "3_3") (pintype "input"))
      (node (ref "S1") (pin "3") (pinfunction "3_3") (pintype "input"))
      (node (ref "S2") (pin "3") (pinfunction "3_3") (pintype "input"))
      (node (ref "SW0") (pin "1") (pinfunction "1_1") (pintype "input"))
      (node (ref "SW0") (pin "2") (pinfunction "2_2") (pintype "input"))
      (node (ref "SW1") (pin "1") (pinfunction "1_1") (pintype "input"))
      (node (ref "SW1") (pin "2") (pinfunction "2_2") (pintype "input"))
      (node (ref "SW2") (pin "1") (pinfunction "1_1") (pintype "input"))
      (node (ref "SW2") (pin "2") (pinfunction "2_2") (pintype "input"))
      (node (ref "SW3") (pin "1") (pinfunction "1_1") (pintype "input"))
      (node (ref "SW3") (pin "2") (pinfunction "2_2") (pintype "input"))
      (node (ref "SW4") (pin "1") (pinfunction "1_1") (pintype "input"))
      (node (ref "SW4") (pin "2") (pinfunction "2_2") (pintype "input"))
      (node (ref "SW5") (pin "1") (pinfunction "1_1") (pintype "input"))
      (node (ref "SW5") (pin "2") (pinfunction "2_2") (pintype "input"))
      (node (ref "U1") (pin "22") (pinfunction "GND_22") (pintype "input"))
      (node (ref "U3") (pin "4") (pinfunction "GND_4") (pintype "input"))
      (node (ref "USB1") (pin "5") (pinfunction "GND_5") (pintype "input"))
      (node (ref "USBC1") (pin "A1") (pinfunction "GND_A1") (pintype "input"))
      (node (ref "USBC1") (pin "A12") (pinfunction "GND_A12") (pintype "input"))
      (node (ref "USBC1") (pin "B1") (pinfunction "GND_B1") (pintype "input"))
      (node (ref "USBC1") (pin "B12") (pinfunction "GND_B12") (pintype "input"))
    )
    (net (code "22") (name "LED-B") (class "Default")
      (node (ref "LED-B") (pin "2") (pinfunction "A_2") (pintype "input"))
      (node (ref "U1") (pin "39") (pinfunction "GPIO47_39") (pintype "input"))
    )
    (net (code "23") (name "LED-G") (class "Default")
      (node (ref "LED-G") (pin "1") (pinfunction "A_1") (pintype "input"))
      (node (ref "U1") (pin "6") (pinfunction "GPIO6_6") (pintype "input"))
    )
    (net (code "24") (name "LED-R") (class "Default")
      (node (ref "LED-R") (pin "2") (pinfunction "A_2") (pintype "input"))
      (node (ref "U1") (pin "37") (pinfunction "GPIO45!!!D_37") (pintype "input"))
    )
    (net (code "25") (name "LED-Y") (class "Default")
      (node (ref "R13") (pin "2") (pinfunction "2_2") (pintype "input"))
      (node (ref "U1") (pin "36") (pinfunction "GPIO0!!!U_36") (pintype "input"))
    )
    (net (code "26") (name "Net-(C4-Pad2)") (class "Default")
      (node (ref "C4") (pin "2") (pinfunction "2_2") (pintype "input"))
      (node (ref "R10") (pin "1") (pinfunction "1_1") (pintype "input"))
      (node (ref "R18") (pin "2") (pinfunction "2_2") (pintype "input"))
    )
    (net (code "27") (name "Net-(C5-Pad2)") (class "Default")
      (node (ref "C5") (pin "2") (pinfunction "2_2") (pintype "input"))
      (node (ref "R11") (pin "1") (pinfunction "1_1") (pintype "input"))
      (node (ref "R19") (pin "2") (pinfunction "2_2") (pintype "input"))
    )
    (net (code "28") (name "Net-(C6-Pad2)") (class "Default")
      (node (ref "C6") (pin "2") (pinfunction "2_2") (pintype "input"))
      (node (ref "R12") (pin "1") (pinfunction "1_1") (pintype "input"))
      (node (ref "R20") (pin "2") (pinfunction "2_2") (pintype "input"))
    )
    (net (code "29") (name "Net-(C7-Pad2)") (class "Default")
      (node (ref "C7") (pin "2") (pinfunction "2_2") (pintype "input"))
      (node (ref "POT-0") (pin "2") (pinfunction "2_2") (pintype "input"))
      (node (ref "R14") (pin "2") (pinfunction "2_2") (pintype "input"))
    )
    (net (code "30") (name "Net-(C8-Pad2)") (class "Default")
      (node (ref "C8") (pin "2") (pinfunction "2_2") (pintype "input"))
      (node (ref "POT-1") (pin "2") (pinfunction "2_2") (pintype "input"))
      (node (ref "R15") (pin "2") (pinfunction "2_2") (pintype "input"))
    )
    (net (code "31") (name "Net-(D1-K)") (class "Default")
      (node (ref "D1") (pin "2") (pinfunction "K_2") (pintype "input"))
      (node (ref "U1") (pin "21") (pinfunction "5V_21") (pintype "input"))
    )
    (net (code "32") (name "Net-(DIGILENT0-Pad1)") (class "Default")
      (node (ref "DIGILENT0") (pin "1") (pinfunction "1_1") (pintype "input"))
      (node (ref "R30") (pin "2") (pinfunction "2_2") (pintype "input"))
    )
    (net (code "33") (name "Net-(DIGILENT0-Pad2)") (class "Default")
      (node (ref "DIGILENT0") (pin "2") (pinfunction "2_2") (pintype "input"))
      (node (ref "R31") (pin "1") (pinfunction "1_1") (pintype "input"))
    )
    (net (code "34") (name "Net-(DIGILENT0-Pad3)") (class "Default")
      (node (ref "DIGILENT0") (pin "3") (pinfunction "3_3") (pintype "input"))
      (node (ref "R29") (pin "2") (pinfunction "2_2") (pintype "input"))
    )
    (net (code "35") (name "Net-(DIGILENT0-Pad4)") (class "Default")
      (node (ref "DIGILENT0") (pin "4") (pinfunction "4_4") (pintype "input"))
      (node (ref "R32") (pin "1") (pinfunction "1_1") (pintype "input"))
    )
    (net (code "36") (name "Net-(DIGILENT0-Pad5)") (class "Default")
      (node (ref "DIGILENT0") (pin "5") (pinfunction "5_5") (pintype "input"))
      (node (ref "R28") (pin "2") (pinfunction "2_2") (pintype "input"))
    )
    (net (code "37") (name "Net-(DIGILENT0-Pad6)") (class "Default")
      (node (ref "DIGILENT0") (pin "6") (pinfunction "6_6") (pintype "input"))
      (node (ref "R33") (pin "1") (pinfunction "1_1") (pintype "input"))
    )
    (net (code "38") (name "Net-(DIGILENT0-Pad7)") (class "Default")
      (node (ref "DIGILENT0") (pin "7") (pinfunction "7_7") (pintype "input"))
      (node (ref "R27") (pin "2") (pinfunction "2_2") (pintype "input"))
    )
    (net (code "39") (name "Net-(DIGILENT0-Pad8)") (class "Default")
      (node (ref "DIGILENT0") (pin "8") (pinfunction "8_8") (pintype "input"))
      (node (ref "R34") (pin "1") (pinfunction "1_1") (pintype "input"))
    )
    (net (code "40") (name "Net-(DIGILENT1-Pad1)") (class "Default")
      (node (ref "DIGILENT1") (pin "1") (pinfunction "1_1") (pintype "input"))
      (node (ref "R35") (pin "2") (pinfunction "2_2") (pintype "input"))
    )
    (net (code "41") (name "Net-(DIGILENT1-Pad2)") (class "Default")
      (node (ref "DIGILENT1") (pin "2") (pinfunction "2_2") (pintype "input"))
      (node (ref "R39") (pin "1") (pinfunction "1_1") (pintype "input"))
    )
    (net (code "42") (name "Net-(DIGILENT1-Pad3)") (class "Default")
      (node (ref "DIGILENT1") (pin "3") (pinfunction "3_3") (pintype "input"))
      (node (ref "R36") (pin "2") (pinfunction "2_2") (pintype "input"))
    )
    (net (code "43") (name "Net-(DIGILENT1-Pad4)") (class "Default")
      (node (ref "DIGILENT1") (pin "4") (pinfunction "4_4") (pintype "input"))
      (node (ref "R40") (pin "1") (pinfunction "1_1") (pintype "input"))
    )
    (net (code "44") (name "Net-(DIGILENT1-Pad5)") (class "Default")
      (node (ref "DIGILENT1") (pin "5") (pinfunction "5_5") (pintype "input"))
      (node (ref "R37") (pin "2") (pinfunction "2_2") (pintype "input"))
    )
    (net (code "45") (name "Net-(DIGILENT1-Pad6)") (class "Default")
      (node (ref "DIGILENT1") (pin "6") (pinfunction "6_6") (pintype "input"))
      (node (ref "R41") (pin "1") (pinfunction "1_1") (pintype "input"))
    )
    (net (code "46") (name "Net-(DIGILENT1-Pad7)") (class "Default")
      (node (ref "DIGILENT1") (pin "7") (pinfunction "7_7") (pintype "input"))
      (node (ref "R38") (pin "2") (pinfunction "2_2") (pintype "input"))
    )
    (net (code "47") (name "Net-(DIGILENT1-Pad8)") (class "Default")
      (node (ref "DIGILENT1") (pin "8") (pinfunction "8_8") (pintype "input"))
      (node (ref "R42") (pin "1") (pinfunction "1_1") (pintype "input"))
    )
    (net (code "48") (name "Net-(LED-B-K)") (class "Default")
      (node (ref "LED-B") (pin "1") (pinfunction "K_1") (pintype "input"))
      (node (ref "R3") (pin "1") (pinfunction "1_1") (pintype "input"))
    )
    (net (code "49") (name "Net-(LED-G-K)") (class "Default")
      (node (ref "LED-G") (pin "2") (pinfunction "K_2") (pintype "input"))
      (node (ref "R2") (pin "1") (pinfunction "1_1") (pintype "input"))
    )
    (net (code "50") (name "Net-(LED-R-K)") (class "Default")
      (node (ref "LED-R") (pin "1") (pinfunction "K_1") (pintype "input"))
      (node (ref "R1") (pin "1") (pinfunction "1_1") (pintype "input"))
    )
    (net (code "51") (name "Net-(LED-RGB-B)") (class "Default")
      (node (ref "LED-RGB") (pin "4") (pinfunction "B_4") (pintype "input"))
      (node (ref "R7") (pin "2") (pinfunction "2_2") (pintype "input"))
    )
    (net (code "52") (name "Net-(LED-RGB-G)") (class "Default")
      (node (ref "LED-RGB") (pin "3") (pinfunction "G_3") (pintype "input"))
      (node (ref "R6") (pin "2") (pinfunction "2_2") (pintype "input"))
    )
    (net (code "53") (name "Net-(LED-RGB-R)") (class "Default")
      (node (ref "LED-RGB") (pin "1") (pinfunction "R_1") (pintype "input"))
      (node (ref "R5") (pin "2") (pinfunction "2_2") (pintype "input"))
    )
    (net (code "54") (name "Net-(LED-Y-K)") (class "Default")
      (node (ref "LED-Y") (pin "1") (pinfunction "K_1") (pintype "input"))
      (node (ref "R4") (pin "1") (pinfunction "1_1") (pintype "input"))
    )
    (net (code "55") (name "Net-(Q1-D)") (class "Default")
      (node (ref "Q1") (pin "3") (pinfunction "D_3") (pintype "input"))
      (node (ref "R4") (pin "2") (pinfunction "2_2") (pintype "input"))
    )
    (net (code "56") (name "Net-(Q1-G)") (class "Default")
      (node (ref "Q1") (pin "1") (pinfunction "G_1") (pintype "input"))
      (node (ref "R13") (pin "1") (pinfunction "1_1") (pintype "input"))
    )
    (net (code "57") (name "Net-(Q2-D)") (class "Default")
      (node (ref "BUZZER2") (pin "1") (pinfunction "1_1") (pintype "input"))
      (node (ref "Q2") (pin "3") (pinfunction "D_3") (pintype "input"))
      (node (ref "R17") (pin "1") (pinfunction "1_1") (pintype "input"))
    )
    (net (code "58") (name "Net-(Q2-G)") (class "Default")
      (node (ref "Q2") (pin "1") (pinfunction "G_1") (pintype "input"))
      (node (ref "R16") (pin "2") (pinfunction "2_2") (pintype "input"))
    )
    (net (code "59") (name "Net-(R10-Pad2)") (class "Default")
      (node (ref "R10") (pin "2") (pinfunction "2_2") (pintype "input"))
      (node (ref "R21") (pin "1") (pinfunction "1_1") (pintype "input"))
      (node (ref "SW0") (pin "3") (pinfunction "3_3") (pintype "input"))
      (node (ref "SW0") (pin "4") (pinfunction "4_4") (pintype "input"))
      (node (ref "SW3") (pin "3") (pinfunction "3_3") (pintype "input"))
      (node (ref "SW3") (pin "4") (pinfunction "4_4") (pintype "input"))
    )
    (net (code "60") (name "Net-(R11-Pad2)") (class "Default")
      (node (ref "R11") (pin "2") (pinfunction "2_2") (pintype "input"))
      (node (ref "R22") (pin "1") (pinfunction "1_1") (pintype "input"))
      (node (ref "SW1") (pin "3") (pinfunction "3_3") (pintype "input"))
      (node (ref "SW1") (pin "4") (pinfunction "4_4") (pintype "input"))
      (node (ref "SW4") (pin "3") (pinfunction "3_3") (pintype "input"))
      (node (ref "SW4") (pin "4") (pinfunction "4_4") (pintype "input"))
    )
    (net (code "61") (name "Net-(R12-Pad2)") (class "Default")
      (node (ref "R12") (pin "2") (pinfunction "2_2") (pintype "input"))
      (node (ref "R23") (pin "1") (pinfunction "1_1") (pintype "input"))
      (node (ref "SW2") (pin "3") (pinfunction "3_3") (pintype "input"))
      (node (ref "SW2") (pin "4") (pinfunction "4_4") (pintype "input"))
      (node (ref "SW5") (pin "3") (pinfunction "3_3") (pintype "input"))
      (node (ref "SW5") (pin "4") (pinfunction "4_4") (pintype "input"))
    )
    (net (code "62") (name "Net-(R24-Pad2)") (class "Default")
      (node (ref "R24") (pin "2") (pinfunction "2_2") (pintype "input"))
      (node (ref "S0") (pin "1") (pinfunction "1_1") (pintype "input"))
    )
    (net (code "63") (name "Net-(R25-Pad2)") (class "Default")
      (node (ref "R25") (pin "2") (pinfunction "2_2") (pintype "input"))
      (node (ref "S1") (pin "1") (pinfunction "1_1") (pintype "input"))
    )
    (net (code "64") (name "Net-(R26-Pad2)") (class "Default")
      (node (ref "R26") (pin "2") (pinfunction "2_2") (pintype "input"))
      (node (ref "S2") (pin "1") (pinfunction "1_1") (pintype "input"))
    )
    (net (code "65") (name "Net-(USBC1-CC1)") (class "Default")
      (node (ref "R51") (pin "2") (pinfunction "2_2") (pintype "input"))
      (node (ref "USBC1") (pin "A5") (pinfunction "CC1_A5") (pintype "input"))
    )
    (net (code "66") (name "Net-(USBC1-CC2)") (class "Default")
      (node (ref "R43") (pin "1") (pinfunction "1_1") (pintype "input"))
      (node (ref "USBC1") (pin "B5") (pinfunction "CC2_B5") (pintype "input"))
    )
    (net (code "67") (name "POT0") (class "Default")
      (node (ref "R14") (pin "1") (pinfunction "1_1") (pintype "input"))
      (node (ref "U1") (pin "26") (pinfunction "GPIO1_26") (pintype "input"))
    )
    (net (code "68") (name "POT1") (class "Default")
      (node (ref "R15") (pin "1") (pinfunction "1_1") (pintype "input"))
      (node (ref "U1") (pin "27") (pinfunction "GPIO2_27") (pintype "input"))
    )
    (net (code "69") (name "RGBLED-B") (class "Default")
      (node (ref "R7") (pin "1") (pinfunction "1_1") (pintype "input"))
      (node (ref "U1") (pin "14") (pinfunction "GPIO46!!!D_14") (pintype "input"))
    )
    (net (code "70") (name "RGBLED-G") (class "Default")
      (node (ref "R6") (pin "1") (pinfunction "1_1") (pintype "input"))
      (node (ref "U1") (pin "13") (pinfunction "GPIO3!!!D_13") (pintype "input"))
    )
    (net (code "71") (name "RGBLED-R") (class "Default")
      (node (ref "R5") (pin "1") (pinfunction "1_1") (pintype "input"))
      (node (ref "U1") (pin "40") (pinfunction "GPIO21_40") (pintype "input"))
    )
    (net (code "72") (name "SER0") (class "Default")
      (node (ref "R26") (pin "1") (pinfunction "1_1") (pintype "input"))
      (node (ref "U1") (pin "8") (pinfunction "GPIO15-RTS0_8") (pintype "input"))
    )
    (net (code "73") (name "SER1") (class "Default")
      (node (ref "R25") (pin "1") (pinfunction "1_1") (pintype "input"))
      (node (ref "U1") (pin "9") (pinfunction "GPIO16-CTS0_9") (pintype "input"))
    )
    (net (code "74") (name "SER2") (class "Default")
      (node (ref "R24") (pin "1") (pinfunction "1_1") (pintype "input"))
      (node (ref "U1") (pin "10") (pinfunction "GPIO17-TX1_10") (pintype "input"))
    )
    (net (code "75") (name "SW0") (class "Default")
      (node (ref "R18") (pin "1") (pinfunction "1_1") (pintype "input"))
      (node (ref "U1") (pin "4") (pinfunction "GPIO4_4") (pintype "input"))
    )
    (net (code "76") (name "SW1") (class "Default")
      (node (ref "R19") (pin "1") (pinfunction "1_1") (pintype "input"))
      (node (ref "U1") (pin "5") (pinfunction "GPIO5_5") (pintype "input"))
    )
    (net (code "77") (name "SW2") (class "Default")
      (node (ref "R20") (pin "1") (pinfunction "1_1") (pintype "input"))
      (node (ref "U1") (pin "38") (pinfunction "GPIO48_38") (pintype "input"))
    )
    (net (code "78") (name "VCC") (class "Default")
      (node (ref "C16") (pin "1") (pinfunction "1_1") (pintype "input"))
      (node (ref "C17") (pin "1") (pinfunction "1_1") (pintype "input"))
      (node (ref "LED-Y") (pin "2") (pinfunction "A_2") (pintype "input"))
      (node (ref "POT-0") (pin "1") (pinfunction "1_1") (pintype "input"))
      (node (ref "POT-1") (pin "1") (pinfunction "1_1") (pintype "input"))
      (node (ref "R21") (pin "2") (pinfunction "2_2") (pintype "input"))
      (node (ref "R22") (pin "2") (pinfunction "2_2") (pintype "input"))
      (node (ref "R23") (pin "2") (pinfunction "2_2") (pintype "input"))
      (node (ref "U1") (pin "1") (pinfunction "3V3_1") (pintype "input"))
    )
    (net (code "79") (name "unconnected-(POT-0-Pad4)") (class "Default")
      (node (ref "POT-0") (pin "4") (pinfunction "4_4") (pintype "input+no_connect"))
    )
    (net (code "80") (name "unconnected-(POT-0-Pad5)") (class "Default")
      (node (ref "POT-0") (pin "5") (pinfunction "5_5") (pintype "input+no_connect"))
    )
    (net (code "81") (name "unconnected-(POT-1-Pad4)") (class "Default")
      (node (ref "POT-1") (pin "4") (pinfunction "4_4") (pintype "input+no_connect"))
    )
    (net (code "82") (name "unconnected-(POT-1-Pad5)") (class "Default")
      (node (ref "POT-1") (pin "5") (pinfunction "5_5") (pintype "input+no_connect"))
    )
    (net (code "83") (name "unconnected-(U1-GPIO43-TX0-Pad24)") (class "Default")
      (node (ref "U1") (pin "24") (pinfunction "GPIO43-TX0_24") (pintype "input"))
    )
    (net (code "84") (name "unconnected-(U1-GPIO44-RX0-Pad25)") (class "Default")
      (node (ref "U1") (pin "25") (pinfunction "GPIO44-RX0_25") (pintype "input"))
    )
    (net (code "85") (name "unconnected-(U1-RST-Pad3)") (class "Default")
      (node (ref "U1") (pin "3") (pinfunction "RST_3") (pintype "input+no_connect"))
    )
    (net (code "86") (name "unconnected-(USB1-ID-Pad4)") (class "Default")
      (node (ref "USB1") (pin "4") (pinfunction "ID_4") (pintype "input"))
    )
    (net (code "87") (name "unconnected-(USB1-SHELL-Pad6)") (class "Default")
      (node (ref "USB1") (pin "6") (pinfunction "SHELL_6") (pintype "input+no_connect"))
    )
    (net (code "88") (name "unconnected-(USBC1-SBU1-PadA8)") (class "Default")
      (node (ref "USBC1") (pin "A8") (pinfunction "SBU1_A8") (pintype "input"))
    )
    (net (code "89") (name "unconnected-(USBC1-SBU2-PadB8)") (class "Default")
      (node (ref "USBC1") (pin "B8") (pinfunction "SBU2_B8") (pintype "input"))
    )
    (net (code "90") (name "unconnected-(USBC1-SH-Pad0)") (class "Default")
      (node (ref "USBC1") (pin "0") (pinfunction "SH_0") (pintype "input"))
    )
  )
)
